# daclock-3_0.net
KiCad netlist of a schematic drawn in EAGLE
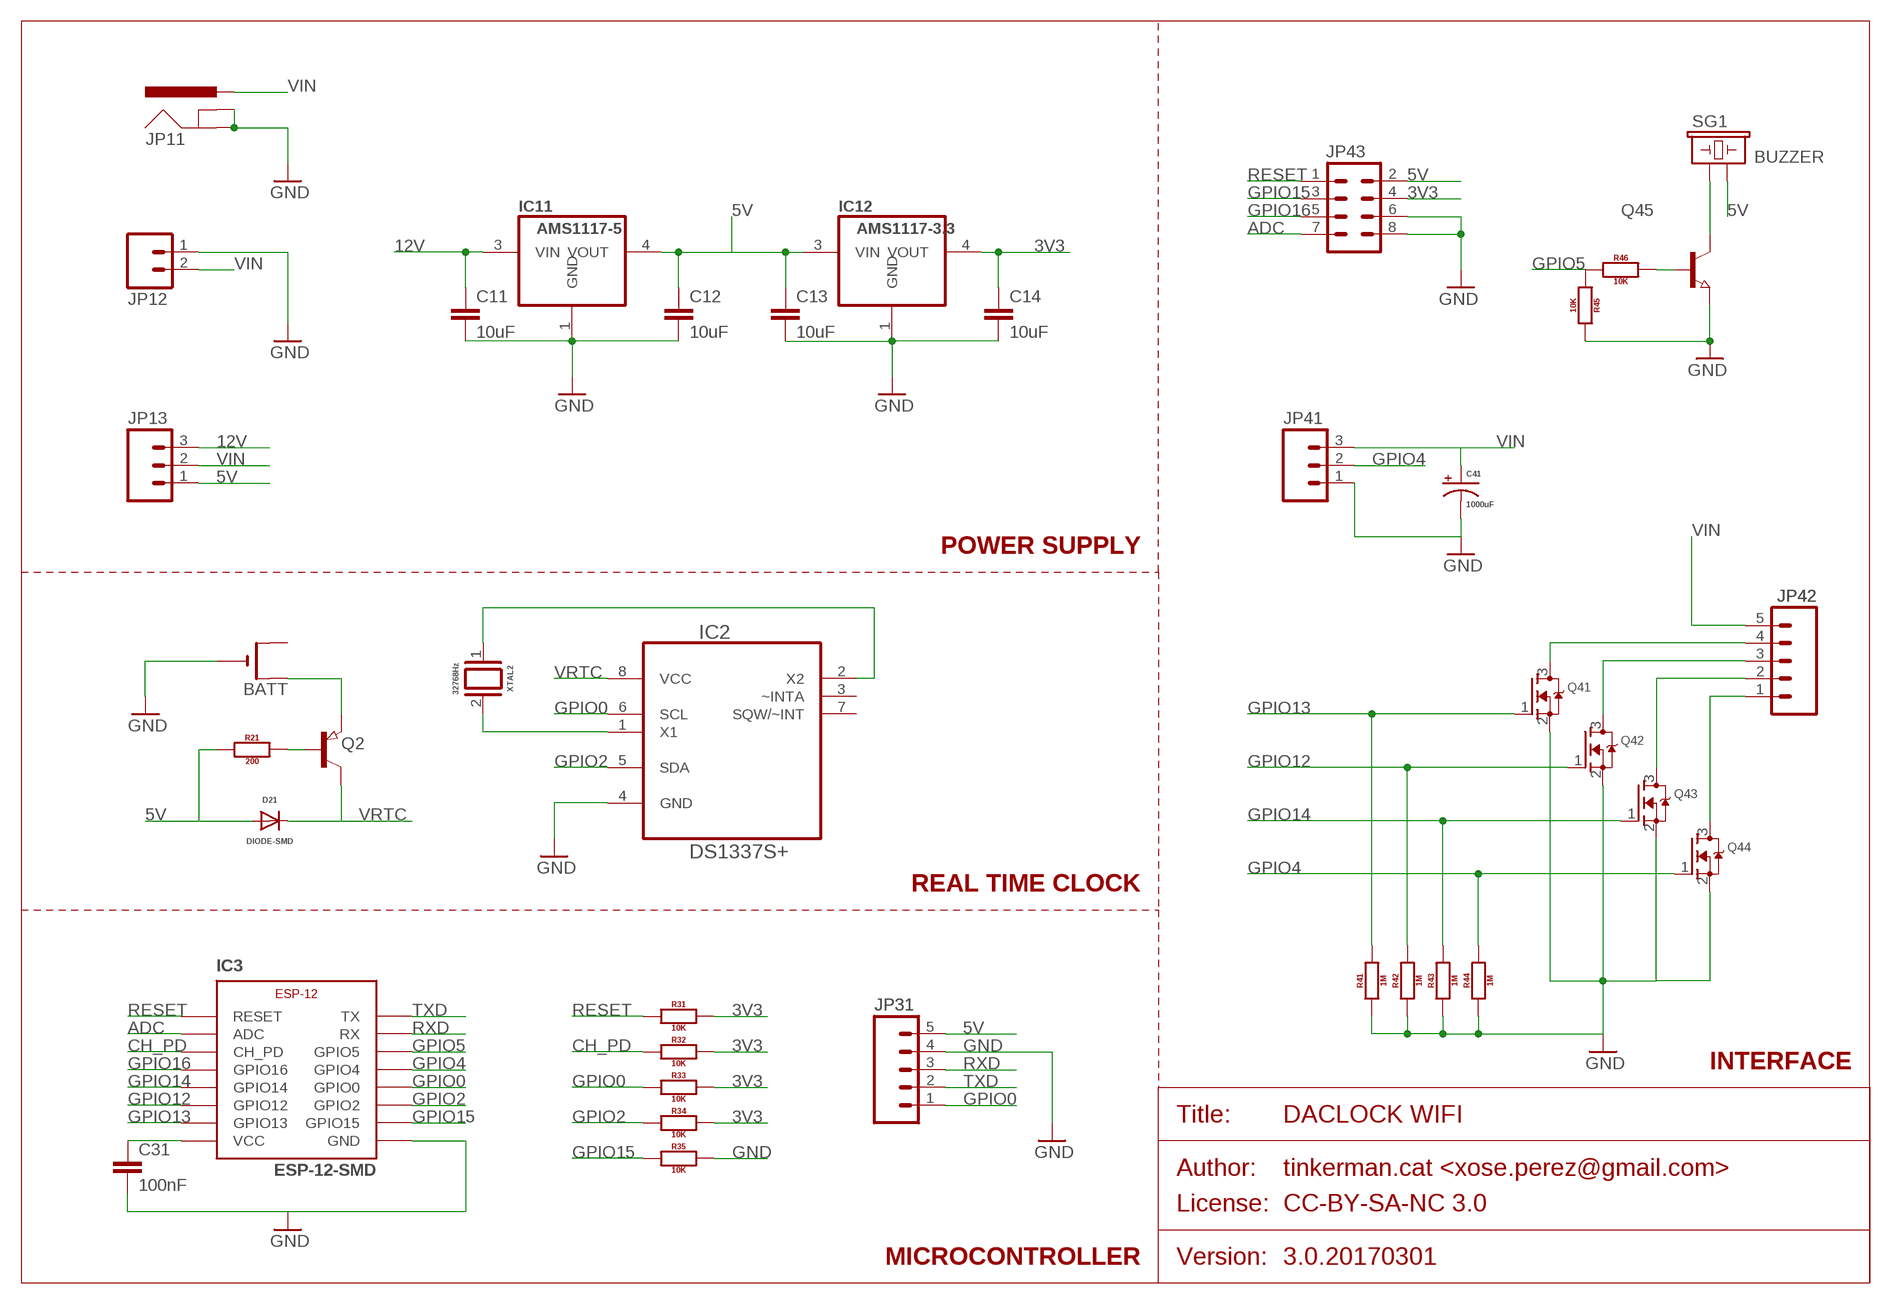
[diagram p0: schematic, sheet 1]

(export (version "E")
  (design (tool "Eeschema 10.0.6"))
  (components
    (comp (ref "BATT")
      (value "CR2032SMT")
      (footprint "eagle-import:CR2032-SMD")
      (libsource (lib "eagle-import") (part "CR2032SMT"))
    )
    (comp (ref "C11")
      (value "10uF")
      (footprint "eagle-import:0805")
      (libsource (lib "eagle-import") (part "C-EU0805"))
    )
    (comp (ref "C12")
      (value "10uF")
      (footprint "eagle-import:0805")
      (libsource (lib "eagle-import") (part "C-EU0805"))
    )
    (comp (ref "C13")
      (value "10uF")
      (footprint "eagle-import:0805")
      (libsource (lib "eagle-import") (part "C-EU0805"))
    )
    (comp (ref "C14")
      (value "10uF")
      (footprint "eagle-import:0805")
      (libsource (lib "eagle-import") (part "C-EU0805"))
    )
    (comp (ref "C31")
      (value "100nF")
      (footprint "eagle-import:0805")
      (libsource (lib "eagle-import") (part "C-EU0805"))
    )
    (comp (ref "C41")
      (value "1000uF")
      (footprint "eagle-import:PANASONIC_G")
      (libsource (lib "eagle-import") (part "CAP_POLG"))
    )
    (comp (ref "D21")
      (value "DIODE-SMD")
      (footprint "eagle-import:0805_DIODE")
      (libsource (lib "eagle-import") (part "DIODE-SMD"))
    )
    (comp (ref "IC2")
      (value "DS1337S+")
      (footprint "eagle-import:SOIC127P600X175-8N")
      (libsource (lib "eagle-import") (part "DS1337S+"))
    )
    (comp (ref "IC3")
      (value "ESP-12-SMD")
      (footprint "eagle-import:ESP-12-SMD")
      (libsource (lib "eagle-import") (part "ESP-12-SMD"))
    )
    (comp (ref "IC11")
      (value "AMS1117-5")
      (footprint "eagle-import:SOT223")
      (libsource (lib "eagle-import") (part "REG1117SOT223-2"))
    )
    (comp (ref "IC12")
      (value "AMS1117-3.3")
      (footprint "eagle-import:SOT223")
      (libsource (lib "eagle-import") (part "REG1117SOT223-2"))
    )
    (comp (ref "JP11")
      (value "POWER_JACKPTH")
      (footprint "eagle-import:POWER_JACK_PTH")
      (libsource (lib "eagle-import") (part "POWER_JACKPTH"))
    )
    (comp (ref "JP12")
      (value "M02200MIL")
      (footprint "eagle-import:SCREWTERMINAL-200MIL-2")
      (libsource (lib "eagle-import") (part "M02200MIL"))
    )
    (comp (ref "JP13")
      (value "M03PTH")
      (footprint "eagle-import:1X03")
      (libsource (lib "eagle-import") (part "M03PTH"))
    )
    (comp (ref "JP31")
      (value "M05NO_SILK")
      (footprint "eagle-import:1X05_NO_SILK")
      (libsource (lib "eagle-import") (part "M05NO_SILK"))
    )
    (comp (ref "JP41")
      (value "M03200MIL")
      (footprint "eagle-import:SCREWTERMINAL-200MIL-3")
      (libsource (lib "eagle-import") (part "M03200MIL"))
    )
    (comp (ref "JP42")
      (value "M05NO_SILK")
      (footprint "eagle-import:1X05_NO_SILK")
      (libsource (lib "eagle-import") (part "M05NO_SILK"))
    )
    (comp (ref "JP43")
      (value "M04X2")
      (footprint "eagle-import:2X4")
      (libsource (lib "eagle-import") (part "M04X2"))
    )
    (comp (ref "Q2")
      (value "PNP-TRANSISTOR_SOT23")
      (footprint "eagle-import:SOT23")
      (libsource (lib "eagle-import") (part "PNP-TRANSISTOR_SOT23"))
    )
    (comp (ref "Q41")
      (value "MOSFET-NREFLOW")
      (footprint "eagle-import:SOT23")
      (libsource (lib "eagle-import") (part "MOSFET-NREFLOW"))
    )
    (comp (ref "Q42")
      (value "MOSFET-NREFLOW")
      (footprint "eagle-import:SOT23")
      (libsource (lib "eagle-import") (part "MOSFET-NREFLOW"))
    )
    (comp (ref "Q43")
      (value "MOSFET-NREFLOW")
      (footprint "eagle-import:SOT23")
      (libsource (lib "eagle-import") (part "MOSFET-NREFLOW"))
    )
    (comp (ref "Q44")
      (value "MOSFET-NREFLOW")
      (footprint "eagle-import:SOT23")
      (libsource (lib "eagle-import") (part "MOSFET-NREFLOW"))
    )
    (comp (ref "Q45")
      (value "NPN-TRANSISTOR_SOT23")
      (footprint "eagle-import:SOT23")
      (libsource (lib "eagle-import") (part "NPN-TRANSISTOR_SOT23"))
    )
    (comp (ref "R21")
      (value "200")
      (footprint "eagle-import:0805")
      (libsource (lib "eagle-import") (part "RESISTOR0805"))
    )
    (comp (ref "R31")
      (value "10K")
      (footprint "eagle-import:0805")
      (libsource (lib "eagle-import") (part "RESISTOR0805"))
    )
    (comp (ref "R32")
      (value "10K")
      (footprint "eagle-import:0805")
      (libsource (lib "eagle-import") (part "RESISTOR0805"))
    )
    (comp (ref "R33")
      (value "10K")
      (footprint "eagle-import:0805")
      (libsource (lib "eagle-import") (part "RESISTOR0805"))
    )
    (comp (ref "R34")
      (value "10K")
      (footprint "eagle-import:0805")
      (libsource (lib "eagle-import") (part "RESISTOR0805"))
    )
    (comp (ref "R35")
      (value "10K")
      (footprint "eagle-import:0805")
      (libsource (lib "eagle-import") (part "RESISTOR0805"))
    )
    (comp (ref "R41")
      (value "1M")
      (footprint "eagle-import:0805")
      (libsource (lib "eagle-import") (part "RESISTOR0805"))
    )
    (comp (ref "R42")
      (value "1M")
      (footprint "eagle-import:0805")
      (libsource (lib "eagle-import") (part "RESISTOR0805"))
    )
    (comp (ref "R43")
      (value "1M")
      (footprint "eagle-import:0805")
      (libsource (lib "eagle-import") (part "RESISTOR0805"))
    )
    (comp (ref "R44")
      (value "1M")
      (footprint "eagle-import:0805")
      (libsource (lib "eagle-import") (part "RESISTOR0805"))
    )
    (comp (ref "R45")
      (value "10K")
      (footprint "eagle-import:0805")
      (libsource (lib "eagle-import") (part "RESISTOR0805"))
    )
    (comp (ref "R46")
      (value "10K")
      (footprint "eagle-import:0805")
      (libsource (lib "eagle-import") (part "RESISTOR0805"))
    )
    (comp (ref "SG1")
      (value "BUZZER")
      (footprint "eagle-import:BUZZER-12MM")
      (libsource (lib "eagle-import") (part "BUZZERPTH"))
    )
    (comp (ref "XTAL2")
      (value "32768Hz")
      (footprint "eagle-import:TC38H")
      (libsource (lib "eagle-import") (part "CRYSTAL_TC38H"))
    )
  )
  (nets
    (net (code "1") (name "/3V3") (class "Default")
      (node (ref "C14") (pin "1") (pinfunction "1_1") (pintype "passive"))
      (node (ref "C31") (pin "1") (pinfunction "1_1") (pintype "passive"))
      (node (ref "IC12") (pin "4") (pinfunction "VOUT_4") (pintype "output"))
      (node (ref "IC3") (pin "VCC") (pinfunction "VCC_VCC") (pintype "bidirectional"))
      (node (ref "JP43") (pin "4") (pinfunction "4_4") (pintype "passive"))
      (node (ref "R31") (pin "2") (pinfunction "2_2") (pintype "passive"))
      (node (ref "R32") (pin "2") (pinfunction "2_2") (pintype "passive"))
      (node (ref "R33") (pin "2") (pinfunction "2_2") (pintype "passive"))
      (node (ref "R34") (pin "2") (pinfunction "2_2") (pintype "passive"))
    )
    (net (code "2") (name "/5V") (class "Default")
      (node (ref "C12") (pin "1") (pinfunction "1_1") (pintype "passive"))
      (node (ref "C13") (pin "1") (pinfunction "1_1") (pintype "passive"))
      (node (ref "D21") (pin "A") (pinfunction "A_A") (pintype "passive"))
      (node (ref "IC11") (pin "4") (pinfunction "VOUT_4") (pintype "output"))
      (node (ref "IC12") (pin "3") (pinfunction "VIN_3") (pintype "input"))
      (node (ref "JP13") (pin "1") (pinfunction "1_1") (pintype "passive"))
      (node (ref "JP31") (pin "5") (pinfunction "5_5") (pintype "passive"))
      (node (ref "JP43") (pin "2") (pinfunction "2_2") (pintype "passive"))
      (node (ref "R21") (pin "1") (pinfunction "1_1") (pintype "passive"))
      (node (ref "SG1") (pin "-") (pinfunction "2_-") (pintype "passive"))
    )
    (net (code "3") (name "/12V") (class "Default")
      (node (ref "C11") (pin "1") (pinfunction "1_1") (pintype "passive"))
      (node (ref "IC11") (pin "3") (pinfunction "VIN_3") (pintype "input"))
      (node (ref "JP13") (pin "3") (pinfunction "3_3") (pintype "passive"))
    )
    (net (code "4") (name "/ADC") (class "Default")
      (node (ref "IC3") (pin "ADC") (pinfunction "ADC_ADC") (pintype "bidirectional"))
      (node (ref "JP43") (pin "7") (pinfunction "7_7") (pintype "passive"))
    )
    (net (code "5") (name "/CH_PD") (class "Default")
      (node (ref "IC3") (pin "CH_PD") (pinfunction "CH_PD_CH_PD") (pintype "bidirectional"))
      (node (ref "R32") (pin "1") (pinfunction "1_1") (pintype "passive"))
    )
    (net (code "6") (name "/GPIO0") (class "Default")
      (node (ref "IC2") (pin "6") (pinfunction "SCL_6") (pintype "input"))
      (node (ref "IC3") (pin "GPIO0") (pinfunction "GPIO0_GPIO0") (pintype "bidirectional"))
      (node (ref "JP31") (pin "1") (pinfunction "1_1") (pintype "passive"))
      (node (ref "R33") (pin "1") (pinfunction "1_1") (pintype "passive"))
    )
    (net (code "7") (name "/GPIO2") (class "Default")
      (node (ref "IC2") (pin "5") (pinfunction "SDA_5") (pintype "bidirectional"))
      (node (ref "IC3") (pin "GPIO2") (pinfunction "GPIO2_GPIO2") (pintype "bidirectional"))
      (node (ref "R34") (pin "1") (pinfunction "1_1") (pintype "passive"))
    )
    (net (code "8") (name "/GPIO4") (class "Default")
      (node (ref "IC3") (pin "GPIO4") (pinfunction "GPIO4_GPIO4") (pintype "bidirectional"))
      (node (ref "JP41") (pin "2") (pinfunction "2_2") (pintype "passive"))
      (node (ref "Q44") (pin "1") (pinfunction "G_1") (pintype "bidirectional"))
      (node (ref "R44") (pin "2") (pinfunction "2_2") (pintype "passive"))
    )
    (net (code "9") (name "/GPIO5") (class "Default")
      (node (ref "IC3") (pin "GPIO5") (pinfunction "GPIO5_GPIO5") (pintype "bidirectional"))
      (node (ref "R45") (pin "1") (pinfunction "1_1") (pintype "passive"))
      (node (ref "R46") (pin "1") (pinfunction "1_1") (pintype "passive"))
    )
    (net (code "10") (name "/GPIO12") (class "Default")
      (node (ref "IC3") (pin "GPIO12") (pinfunction "GPIO12_GPIO12") (pintype "bidirectional"))
      (node (ref "Q42") (pin "1") (pinfunction "G_1") (pintype "bidirectional"))
      (node (ref "R42") (pin "2") (pinfunction "2_2") (pintype "passive"))
    )
    (net (code "11") (name "/GPIO13") (class "Default")
      (node (ref "IC3") (pin "GPIO13") (pinfunction "GPIO13_GPIO13") (pintype "bidirectional"))
      (node (ref "Q41") (pin "1") (pinfunction "G_1") (pintype "bidirectional"))
      (node (ref "R41") (pin "2") (pinfunction "2_2") (pintype "passive"))
    )
    (net (code "12") (name "/GPIO14") (class "Default")
      (node (ref "IC3") (pin "GPIO14") (pinfunction "GPIO14_GPIO14") (pintype "bidirectional"))
      (node (ref "Q43") (pin "1") (pinfunction "G_1") (pintype "bidirectional"))
      (node (ref "R43") (pin "2") (pinfunction "2_2") (pintype "passive"))
    )
    (net (code "13") (name "/GPIO15") (class "Default")
      (node (ref "IC3") (pin "GPIO15") (pinfunction "GPIO15_GPIO15") (pintype "bidirectional"))
      (node (ref "JP43") (pin "3") (pinfunction "3_3") (pintype "passive"))
      (node (ref "R35") (pin "1") (pinfunction "1_1") (pintype "passive"))
    )
    (net (code "14") (name "/GPIO16") (class "Default")
      (node (ref "IC3") (pin "GPIO16") (pinfunction "GPIO16_GPIO16") (pintype "bidirectional"))
      (node (ref "JP43") (pin "5") (pinfunction "5_5") (pintype "passive"))
    )
    (net (code "15") (name "/RESET") (class "Default")
      (node (ref "IC3") (pin "RESET") (pinfunction "RESET_RESET") (pintype "bidirectional"))
      (node (ref "JP43") (pin "1") (pinfunction "1_1") (pintype "passive"))
      (node (ref "R31") (pin "1") (pinfunction "1_1") (pintype "passive"))
    )
    (net (code "16") (name "/RXD") (class "Default")
      (node (ref "IC3") (pin "RX") (pinfunction "RX_RX") (pintype "bidirectional"))
      (node (ref "JP31") (pin "3") (pinfunction "3_3") (pintype "passive"))
    )
    (net (code "17") (name "/TXD") (class "Default")
      (node (ref "IC3") (pin "TX") (pinfunction "TX_TX") (pintype "bidirectional"))
      (node (ref "JP31") (pin "2") (pinfunction "2_2") (pintype "passive"))
    )
    (net (code "18") (name "/VIN") (class "Default")
      (node (ref "C41") (pin "+") (pinfunction "+_+") (pintype "passive"))
      (node (ref "JP11") (pin "PWR") (pinfunction "PWR_PWR") (pintype "bidirectional"))
      (node (ref "JP12") (pin "2") (pinfunction "2_2") (pintype "passive"))
      (node (ref "JP13") (pin "2") (pinfunction "2_2") (pintype "passive"))
      (node (ref "JP41") (pin "3") (pinfunction "3_3") (pintype "passive"))
      (node (ref "JP42") (pin "5") (pinfunction "5_5") (pintype "passive"))
    )
    (net (code "19") (name "/VRTC") (class "Default")
      (node (ref "D21") (pin "C") (pinfunction "C_C") (pintype "passive"))
      (node (ref "IC2") (pin "8") (pinfunction "VCC_8") (pintype "power_in"))
      (node (ref "Q2") (pin "3") (pinfunction "C_3") (pintype "passive"))
    )
    (net (code "20") (name "GND") (class "Default")
      (node (ref "BATT") (pin "-") (pinfunction "-_-") (pintype "passive"))
      (node (ref "C11") (pin "2") (pinfunction "2_2") (pintype "passive"))
      (node (ref "C12") (pin "2") (pinfunction "2_2") (pintype "passive"))
      (node (ref "C13") (pin "2") (pinfunction "2_2") (pintype "passive"))
      (node (ref "C14") (pin "2") (pinfunction "2_2") (pintype "passive"))
      (node (ref "C31") (pin "2") (pinfunction "2_2") (pintype "passive"))
      (node (ref "C41") (pin "-") (pinfunction "-_-") (pintype "passive"))
      (node (ref "IC11") (pin "1") (pinfunction "GND_1") (pintype "power_in"))
      (node (ref "IC12") (pin "1") (pinfunction "GND_1") (pintype "power_in"))
      (node (ref "IC2") (pin "4") (pinfunction "GND_4") (pintype "passive"))
      (node (ref "IC3") (pin "GND") (pinfunction "GND_GND") (pintype "bidirectional"))
      (node (ref "JP11") (pin "GND") (pinfunction "GND_GND") (pintype "bidirectional"))
      (node (ref "JP11") (pin "GNDBREAK") (pinfunction "GNDBREAK_GNDBREAK") (pintype "bidirectional"))
      (node (ref "JP12") (pin "1") (pinfunction "1_1") (pintype "passive"))
      (node (ref "JP31") (pin "4") (pinfunction "4_4") (pintype "passive"))
      (node (ref "JP41") (pin "1") (pinfunction "1_1") (pintype "passive"))
      (node (ref "JP43") (pin "6") (pinfunction "6_6") (pintype "passive"))
      (node (ref "JP43") (pin "8") (pinfunction "8_8") (pintype "passive"))
      (node (ref "Q41") (pin "2") (pinfunction "S_2") (pintype "bidirectional"))
      (node (ref "Q42") (pin "2") (pinfunction "S_2") (pintype "bidirectional"))
      (node (ref "Q43") (pin "2") (pinfunction "S_2") (pintype "bidirectional"))
      (node (ref "Q44") (pin "2") (pinfunction "S_2") (pintype "bidirectional"))
      (node (ref "Q45") (pin "2") (pinfunction "E_2") (pintype "passive"))
      (node (ref "R35") (pin "2") (pinfunction "2_2") (pintype "passive"))
      (node (ref "R41") (pin "1") (pinfunction "1_1") (pintype "passive"))
      (node (ref "R42") (pin "1") (pinfunction "1_1") (pintype "passive"))
      (node (ref "R43") (pin "1") (pinfunction "1_1") (pintype "passive"))
      (node (ref "R44") (pin "1") (pinfunction "1_1") (pintype "passive"))
      (node (ref "R45") (pin "2") (pinfunction "2_2") (pintype "passive"))
    )
    (net (code "21") (name "Net-(BATT-+)") (class "Default")
      (node (ref "BATT") (pin "+$1") (pinfunction "+_+$1") (pintype "passive"))
      (node (ref "Q2") (pin "2") (pinfunction "E_2") (pintype "passive"))
    )
    (net (code "22") (name "Net-(IC2-X1)") (class "Default")
      (node (ref "IC2") (pin "1") (pinfunction "X1_1") (pintype "input"))
      (node (ref "XTAL2") (pin "2") (pinfunction "2_2") (pintype "passive"))
    )
    (net (code "23") (name "Net-(IC2-X2)") (class "Default")
      (node (ref "IC2") (pin "2") (pinfunction "X2_2") (pintype "passive"))
      (node (ref "XTAL2") (pin "1") (pinfunction "1_1") (pintype "passive"))
    )
    (net (code "24") (name "Net-(Q2-B)") (class "Default")
      (node (ref "Q2") (pin "1") (pinfunction "B_1") (pintype "passive"))
      (node (ref "R21") (pin "2") (pinfunction "2_2") (pintype "passive"))
    )
    (net (code "25") (name "Net-(Q41-D)") (class "Default")
      (node (ref "JP42") (pin "4") (pinfunction "4_4") (pintype "passive"))
      (node (ref "Q41") (pin "3") (pinfunction "D_3") (pintype "bidirectional"))
    )
    (net (code "26") (name "Net-(Q42-D)") (class "Default")
      (node (ref "JP42") (pin "3") (pinfunction "3_3") (pintype "passive"))
      (node (ref "Q42") (pin "3") (pinfunction "D_3") (pintype "bidirectional"))
    )
    (net (code "27") (name "Net-(Q43-D)") (class "Default")
      (node (ref "JP42") (pin "2") (pinfunction "2_2") (pintype "passive"))
      (node (ref "Q43") (pin "3") (pinfunction "D_3") (pintype "bidirectional"))
    )
    (net (code "28") (name "Net-(Q44-D)") (class "Default")
      (node (ref "JP42") (pin "1") (pinfunction "1_1") (pintype "passive"))
      (node (ref "Q44") (pin "3") (pinfunction "D_3") (pintype "bidirectional"))
    )
    (net (code "29") (name "Net-(Q45-B)") (class "Default")
      (node (ref "Q45") (pin "1") (pinfunction "B_1") (pintype "passive"))
      (node (ref "R46") (pin "2") (pinfunction "2_2") (pintype "passive"))
    )
    (net (code "30") (name "Net-(Q45-C)") (class "Default")
      (node (ref "Q45") (pin "3") (pinfunction "C_3") (pintype "passive"))
      (node (ref "SG1") (pin "+") (pinfunction "1_+") (pintype "passive"))
    )
    (net (code "31") (name "unconnected-(BATT-+1-Pad+$2)") (class "Default")
      (node (ref "BATT") (pin "+$2") (pinfunction "+1_+$2") (pintype "passive"))
    )
    (net (code "32") (name "unconnected-(IC2-SQW{slash}~{INT}-Pad7)") (class "Default")
      (node (ref "IC2") (pin "7") (pinfunction "SQW/~{INT}_7") (pintype "output"))
    )
    (net (code "33") (name "unconnected-(IC2-~{INTA}-Pad3)") (class "Default")
      (node (ref "IC2") (pin "3") (pinfunction "~{INTA}_3") (pintype "output"))
    )
  )
)
